# schematic3.net
KiCad netlist of a schematic drawn in EAGLE
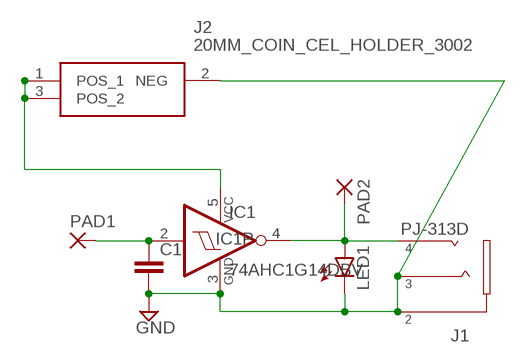
[diagram p0: schematic, sheet 1]

(export (version "E")
  (design (tool "Eeschema 10.0.6"))
  (components
    (comp (ref "C1")
      (value "C-EUC0805")
      (footprint "eagle-import:C0805")
      (libsource (lib "eagle-import") (part "C-EUC0805"))
    )
    (comp (ref "IC1")
      (value "74AHC1G14DBV")
      (footprint "eagle-import:SOT23-5")
      (libsource (lib "eagle-import") (part "741G14DBVAHC"))
    )
    (comp (ref "J1")
      (value "PJ-313D")
      (footprint "eagle-import:PJ-313D")
      (libsource (lib "eagle-import") (part "PJ-313D"))
    )
    (comp (ref "J2")
      (value "20MM_COIN_CEL_HOLDER_3002")
      (footprint "eagle-import:SMT_CELL_HOLDER")
      (fields (field (name "MANUFACTURER_PART_NUMBER") "3002") (field (name "MOUSER_PART_NUMBER") "534-3002"))
      (libsource (lib "eagle-import") (part "20MM_COIN_CEL_HOLDER_3002"))
    )
    (comp (ref "LED1")
      (value "LEDCHIP-LED0805")
      (footprint "eagle-import:CHIP-LED0805")
      (libsource (lib "eagle-import") (part "LEDCHIP-LED0805"))
    )
    (comp (ref "PAD1")
      (value "SMD5")
      (footprint "eagle-import:SMD2,54-5,08")
      (libsource (lib "eagle-import") (part "SMD5"))
    )
    (comp (ref "PAD2")
      (value "SMD5")
      (footprint "eagle-import:SMD2,54-5,08")
      (libsource (lib "eagle-import") (part "SMD5"))
    )
  )
  (nets
    (net (code "1") (name "GND") (class "Default")
      (node (ref "C1") (pin "2") (pinfunction "2_2") (pintype "passive"))
      (node (ref "IC1") (pin "3") (pinfunction "GND_3") (pintype "power_in"))
      (node (ref "J1") (pin "2_1") (pinfunction "2_2_1") (pintype "passive"))
      (node (ref "J1") (pin "2_2") (pinfunction "2_2_2") (pintype "passive"))
      (node (ref "J1") (pin "3_1") (pinfunction "3_3_1") (pintype "passive"))
      (node (ref "J1") (pin "3_2") (pinfunction "3_3_2") (pintype "passive"))
      (node (ref "J2") (pin "2") (pinfunction "NEG_2") (pintype "bidirectional"))
      (node (ref "LED1") (pin "C") (pinfunction "C_C") (pintype "passive"))
    )
    (net (code "2") (name "Net-(IC1A-I)") (class "Default")
      (node (ref "C1") (pin "1") (pinfunction "1_1") (pintype "passive"))
      (node (ref "IC1") (pin "2") (pinfunction "I_2") (pintype "input"))
      (node (ref "PAD1") (pin "1") (pinfunction "P_1") (pintype "passive"))
    )
    (net (code "3") (name "Net-(IC1A-O)") (class "Default")
      (node (ref "IC1") (pin "4") (pinfunction "O_4") (pintype "output"))
      (node (ref "J1") (pin "4_1") (pinfunction "4_4_1") (pintype "passive"))
      (node (ref "J1") (pin "4_2") (pinfunction "4_4_2") (pintype "passive"))
      (node (ref "LED1") (pin "A") (pinfunction "A_A") (pintype "passive"))
      (node (ref "PAD2") (pin "1") (pinfunction "P_1") (pintype "passive"))
    )
    (net (code "4") (name "Net-(IC1B-VCC)") (class "Default")
      (node (ref "IC1") (pin "5") (pinfunction "VCC_5") (pintype "power_in"))
      (node (ref "J2") (pin "1") (pinfunction "POS_1_1") (pintype "bidirectional"))
      (node (ref "J2") (pin "3") (pinfunction "POS_2_3") (pintype "bidirectional"))
    )
  )
)
